# relayBoardSingleSMD.net
KiCad netlist of a schematic drawn in EAGLE
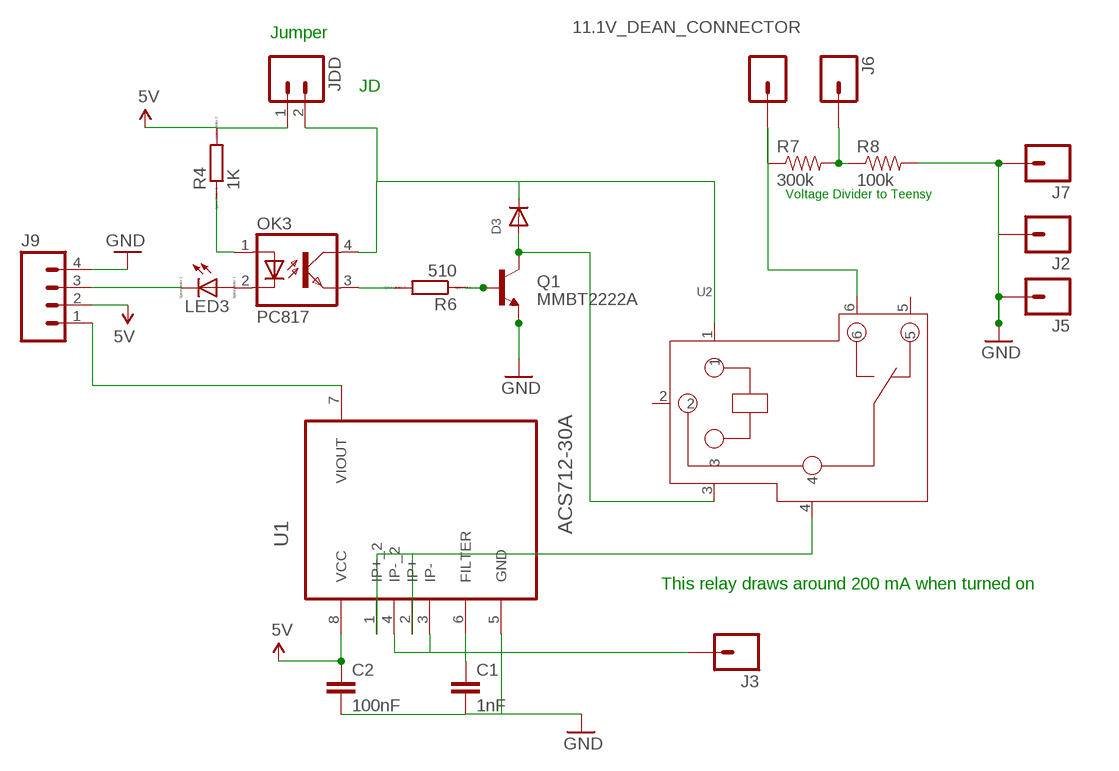
[diagram p0: schematic, sheet 1]

(export (version "E")
  (design (tool "Eeschema 10.0.6"))
  (components
    (comp (ref "11.1V_DEAN_CONNECTOR")
      (value "M01NOSILK-KIT")
      (footprint "eagle-import:1X01NS-KIT")
      (libsource (lib "eagle-import") (part "M01NOSILK-KIT"))
    )
    (comp (ref "C1")
      (value "1nF")
      (footprint "eagle-import:1206")
      (libsource (lib "eagle-import") (part "CAP1206"))
    )
    (comp (ref "C2")
      (value "100nF")
      (footprint "eagle-import:1206")
      (libsource (lib "eagle-import") (part "CAP1206"))
    )
    (comp (ref "D3")
      (value "DIODEDO-1N4148")
      (footprint "eagle-import:DO-1N4148")
      (libsource (lib "eagle-import") (part "DIODEDO-1N4148"))
    )
    (comp (ref "J2")
      (value "M01NOSILK-KIT")
      (footprint "eagle-import:1X01NS-KIT")
      (libsource (lib "eagle-import") (part "M01NOSILK-KIT"))
    )
    (comp (ref "J3")
      (value "M01NOSILK-KIT")
      (footprint "eagle-import:1X01NS-KIT")
      (libsource (lib "eagle-import") (part "M01NOSILK-KIT"))
    )
    (comp (ref "J5")
      (value "M01NOSILK-KIT")
      (footprint "eagle-import:1X01NS-KIT")
      (libsource (lib "eagle-import") (part "M01NOSILK-KIT"))
    )
    (comp (ref "J6")
      (value "M01NOSILK-KIT")
      (footprint "eagle-import:1X01NS-KIT")
      (libsource (lib "eagle-import") (part "M01NOSILK-KIT"))
    )
    (comp (ref "J7")
      (value "M01NOSILK-KIT")
      (footprint "eagle-import:1X01NS-KIT")
      (libsource (lib "eagle-import") (part "M01NOSILK-KIT"))
    )
    (comp (ref "J9")
      (value "M04LOCK_LONGPADS")
      (footprint "eagle-import:1X04_LOCK_LONGPADS")
      (libsource (lib "eagle-import") (part "M04LOCK_LONGPADS"))
    )
    (comp (ref "JDD")
      (value "M02LOCK_LONGPADS")
      (footprint "eagle-import:1X02_LOCK_LONGPADS")
      (libsource (lib "eagle-import") (part "M02LOCK_LONGPADS"))
    )
    (comp (ref "LED3")
      (value "LED_E")
      (footprint "eagle-import:LED_1206")
      (libsource (lib "eagle-import") (part "LED_E"))
    )
    (comp (ref "OK3")
      (value "PC817")
      (footprint "eagle-import:DIL04")
      (fields (field (name "MPN") "PC817X4J000F"))
      (libsource (lib "eagle-import") (part "PC817"))
    )
    (comp (ref "Q1")
      (value "MMBT2222A")
      (footprint "eagle-import:SOT23-3")
      (libsource (lib "eagle-import") (part "TRANSISTOR_NPNMMBT2222A"))
    )
    (comp (ref "R4")
      (value "1K")
      (footprint "eagle-import:R1206")
      (libsource (lib "eagle-import") (part "RR1206"))
    )
    (comp (ref "R6")
      (value "510")
      (footprint "eagle-import:R1206")
      (libsource (lib "eagle-import") (part "RR1206"))
    )
    (comp (ref "R7")
      (value "300k")
      (footprint "eagle-import:1206")
      (libsource (lib "eagle-import") (part "RESISTOR1206"))
    )
    (comp (ref "R8")
      (value "100k")
      (footprint "eagle-import:1206")
      (libsource (lib "eagle-import") (part "RESISTOR1206"))
    )
    (comp (ref "U1")
      (value "ACS712-30A")
      (footprint "eagle-import:SOIC127P600X175-8N")
      (fields (field (name "MPN") "ACS712ELCTR-20A-T"))
      (libsource (lib "eagle-import") (part "ACS712ELCTR-20A-T"))
    )
    (comp (ref "U2")
      (value "RELAY-SLA-05VDC-SL-C")
      (footprint "eagle-import:6P-19.8H")
      (libsource (lib "eagle-import") (part "RELAY-SLA-05VDC-SL-C"))
    )
  )
  (nets
    (net (code "1") (name "5V") (class "Default")
      (node (ref "C2") (pin "1") (pinfunction "1_1") (pintype "passive"))
      (node (ref "J9") (pin "2") (pinfunction "2_2") (pintype "passive"))
      (node (ref "JDD") (pin "1") (pinfunction "1_1") (pintype "passive"))
      (node (ref "R4") (pin "2") (pinfunction "2_2") (pintype "passive"))
      (node (ref "U1") (pin "8") (pinfunction "VCC_8") (pintype "power_in"))
    )
    (net (code "2") (name "GND") (class "Default")
      (node (ref "C1") (pin "2") (pinfunction "2_2") (pintype "passive"))
      (node (ref "C2") (pin "2") (pinfunction "2_2") (pintype "passive"))
      (node (ref "J2") (pin "1") (pinfunction "1_1") (pintype "passive"))
      (node (ref "J5") (pin "1") (pinfunction "1_1") (pintype "passive"))
      (node (ref "J7") (pin "1") (pinfunction "1_1") (pintype "passive"))
      (node (ref "J9") (pin "4") (pinfunction "4_4") (pintype "passive"))
      (node (ref "Q1") (pin "2") (pinfunction "E_2") (pintype "passive"))
      (node (ref "R8") (pin "2") (pinfunction "2_2") (pintype "passive"))
      (node (ref "U1") (pin "5") (pinfunction "GND_5") (pintype "passive"))
    )
    (net (code "3") (name "Net-(11.1V_DEAN_CONNECTOR-Pad1)") (class "Default")
      (node (ref "11.1V_DEAN_CONNECTOR") (pin "1") (pinfunction "1_1") (pintype "passive"))
      (node (ref "R7") (pin "1") (pinfunction "1_1") (pintype "passive"))
      (node (ref "U2") (pin "6") (pinfunction "6_6") (pintype "bidirectional"))
    )
    (net (code "4") (name "Net-(J6-Pad1)") (class "Default")
      (node (ref "J6") (pin "1") (pinfunction "1_1") (pintype "passive"))
      (node (ref "R7") (pin "2") (pinfunction "2_2") (pintype "passive"))
      (node (ref "R8") (pin "1") (pinfunction "1_1") (pintype "passive"))
    )
    (net (code "5") (name "Net-(J9-Pad3)") (class "Default")
      (node (ref "J9") (pin "3") (pinfunction "3_3") (pintype "passive"))
      (node (ref "LED3") (pin "C") (pinfunction "C_C") (pintype "passive"))
    )
    (net (code "6") (name "Net-(OK3-A)") (class "Default")
      (node (ref "OK3") (pin "1") (pinfunction "A_1") (pintype "passive"))
      (node (ref "R4") (pin "1") (pinfunction "1_1") (pintype "passive"))
    )
    (net (code "7") (name "Net-(OK3-C)") (class "Default")
      (node (ref "LED3") (pin "A") (pinfunction "A_A") (pintype "passive"))
      (node (ref "OK3") (pin "2") (pinfunction "C_2") (pintype "passive"))
    )
    (net (code "8") (name "Net-(OK3-COL)") (class "Default")
      (node (ref "D3") (pin "C") (pinfunction "C_C") (pintype "passive"))
      (node (ref "JDD") (pin "2") (pinfunction "2_2") (pintype "passive"))
      (node (ref "OK3") (pin "4") (pinfunction "COL_4") (pintype "passive"))
      (node (ref "U2") (pin "1") (pinfunction "1_1") (pintype "bidirectional"))
    )
    (net (code "9") (name "Net-(OK3-EMIT)") (class "Default")
      (node (ref "OK3") (pin "3") (pinfunction "EMIT_3") (pintype "passive"))
      (node (ref "R6") (pin "2") (pinfunction "2_2") (pintype "passive"))
    )
    (net (code "10") (name "Net-(Q1-B)") (class "Default")
      (node (ref "Q1") (pin "1") (pinfunction "B_1") (pintype "passive"))
      (node (ref "R6") (pin "1") (pinfunction "1_1") (pintype "passive"))
    )
    (net (code "11") (name "Net-(Q1-C)") (class "Default")
      (node (ref "D3") (pin "A") (pinfunction "A_A") (pintype "passive"))
      (node (ref "Q1") (pin "3") (pinfunction "C_3") (pintype "passive"))
      (node (ref "U2") (pin "3") (pinfunction "3_3") (pintype "bidirectional"))
    )
    (net (code "12") (name "Net-(U1-FILTER)") (class "Default")
      (node (ref "C1") (pin "1") (pinfunction "1_1") (pintype "passive"))
      (node (ref "U1") (pin "6") (pinfunction "FILTER_6") (pintype "input"))
    )
    (net (code "13") (name "Net-(U1-IP+)") (class "Default")
      (node (ref "U1") (pin "1") (pinfunction "IP+_2_1") (pintype "input"))
      (node (ref "U1") (pin "2") (pinfunction "IP+_2") (pintype "input"))
      (node (ref "U2") (pin "4") (pinfunction "4_4") (pintype "bidirectional"))
    )
    (net (code "14") (name "Net-(U1-IP-)") (class "Default")
      (node (ref "J3") (pin "1") (pinfunction "1_1") (pintype "passive"))
      (node (ref "U1") (pin "3") (pinfunction "IP-_3") (pintype "input"))
      (node (ref "U1") (pin "4") (pinfunction "IP-_2_4") (pintype "input"))
    )
    (net (code "15") (name "Net-(U1-VIOUT)") (class "Default")
      (node (ref "J9") (pin "1") (pinfunction "1_1") (pintype "passive"))
      (node (ref "U1") (pin "7") (pinfunction "VIOUT_7") (pintype "output"))
    )
    (net (code "16") (name "unconnected-(U2-Pad2)") (class "Default")
      (node (ref "U2") (pin "2") (pinfunction "2_2") (pintype "bidirectional"))
    )
    (net (code "17") (name "unconnected-(U2-Pad5)") (class "Default")
      (node (ref "U2") (pin "5") (pinfunction "5_5") (pintype "bidirectional"))
    )
  )
)
